# leaf_xcvr_rs485_bro.net
KiCad netlist of a schematic drawn in EAGLE
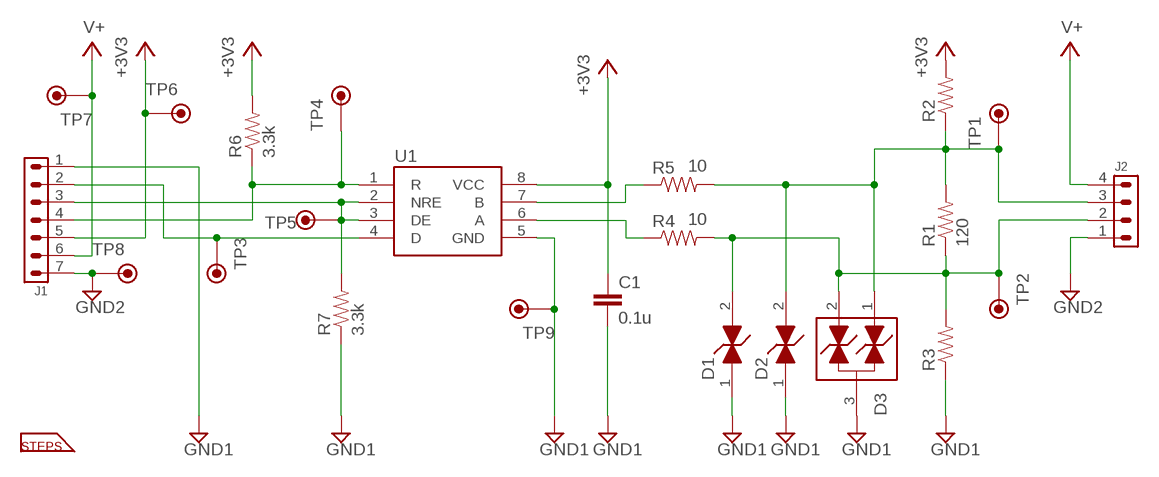
[diagram p0: schematic, sheet 1]

(export (version "E")
  (design (tool "Eeschema 10.0.6"))
  (components
    (comp (ref "C1")
      (value "0.1u")
      (footprint "eagle-import:0603")
      (libsource (lib "eagle-import") (part "0603_CAP"))
    )
    (comp (ref "D1")
      (value "TVS_DO-214AA")
      (footprint "eagle-import:DO-214AA_LITTELFUSE")
      (libsource (lib "eagle-import") (part "TVS_DO-214AA"))
    )
    (comp (ref "D2")
      (value "TVS_DO-214AA")
      (footprint "eagle-import:DO-214AA_LITTELFUSE")
      (libsource (lib "eagle-import") (part "TVS_DO-214AA"))
    )
    (comp (ref "D3")
      (value "TVS_SOT-23")
      (footprint "eagle-import:SOT-23_ONSEMI")
      (libsource (lib "eagle-import") (part "TVS_SOT-23"))
    )
    (comp (ref "J1")
      (value "CONN_7X1_JST_PA")
      (footprint "eagle-import:CONN_7X1_JST_PA")
      (libsource (lib "eagle-import") (part "CONN_7X1_JST_PA"))
    )
    (comp (ref "J2")
      (value "CONN_4X1_JST_PA")
      (footprint "eagle-import:CONN_4X1_JST_PA")
      (libsource (lib "eagle-import") (part "CONN_4X1_JST_PA"))
    )
    (comp (ref "R1")
      (value "120")
      (footprint "eagle-import:0603")
      (libsource (lib "eagle-import") (part "0603_RES"))
    )
    (comp (ref "R2")
      (value "0603_RES")
      (footprint "eagle-import:0603")
      (libsource (lib "eagle-import") (part "0603_RES"))
    )
    (comp (ref "R3")
      (value "0603_RES")
      (footprint "eagle-import:0603")
      (libsource (lib "eagle-import") (part "0603_RES"))
    )
    (comp (ref "R4")
      (value "10")
      (footprint "eagle-import:0603")
      (libsource (lib "eagle-import") (part "0603_RES"))
    )
    (comp (ref "R5")
      (value "10")
      (footprint "eagle-import:0603")
      (libsource (lib "eagle-import") (part "0603_RES"))
    )
    (comp (ref "R6")
      (value "3.3k")
      (footprint "eagle-import:0603")
      (libsource (lib "eagle-import") (part "0603_RES"))
    )
    (comp (ref "R7")
      (value "3.3k")
      (footprint "eagle-import:0603")
      (libsource (lib "eagle-import") (part "0603_RES"))
    )
    (comp (ref "TP1")
      (value "TP1")
      (footprint "eagle-import:TP1")
      (libsource (lib "eagle-import") (part "TP1"))
    )
    (comp (ref "TP2")
      (value "TP1")
      (footprint "eagle-import:TP1")
      (libsource (lib "eagle-import") (part "TP1"))
    )
    (comp (ref "TP3")
      (value "TP1")
      (footprint "eagle-import:TP1")
      (libsource (lib "eagle-import") (part "TP1"))
    )
    (comp (ref "TP4")
      (value "TP1")
      (footprint "eagle-import:TP1")
      (libsource (lib "eagle-import") (part "TP1"))
    )
    (comp (ref "TP5")
      (value "TP1")
      (footprint "eagle-import:TP1")
      (libsource (lib "eagle-import") (part "TP1"))
    )
    (comp (ref "TP6")
      (value "TP1")
      (footprint "eagle-import:TP1")
      (libsource (lib "eagle-import") (part "TP1"))
    )
    (comp (ref "TP7")
      (value "TP1")
      (footprint "eagle-import:TP1")
      (libsource (lib "eagle-import") (part "TP1"))
    )
    (comp (ref "TP8")
      (value "TP1")
      (footprint "eagle-import:TP1")
      (libsource (lib "eagle-import") (part "TP1"))
    )
    (comp (ref "TP9")
      (value "TP1")
      (footprint "eagle-import:TP1")
      (libsource (lib "eagle-import") (part "TP1"))
    )
    (comp (ref "U$1")
      (value "STEPS_LOGO")
      (footprint "eagle-import:STEPS_LOGO")
      (libsource (lib "eagle-import") (part "STEPS_LOGO"))
    )
    (comp (ref "U1")
      (value "RS485_XCVR_SN65HVD178X")
      (footprint "eagle-import:SOIC_08_TI")
      (libsource (lib "eagle-import") (part "RS485_XCVR_SN65HVD178X"))
    )
  )
  (nets
    (net (code "1") (name "+3V3") (class "Default")
      (node (ref "C1") (pin "P$1") (pinfunction "1_P$1") (pintype "passive"))
      (node (ref "J1") (pin "5") (pinfunction "5_5") (pintype "bidirectional"))
      (node (ref "R2") (pin "P$2") (pinfunction "2_P$2") (pintype "passive"))
      (node (ref "R6") (pin "P$2") (pinfunction "2_P$2") (pintype "passive"))
      (node (ref "TP6") (pin "P$1") (pinfunction "P$1_P$1") (pintype "bidirectional"))
      (node (ref "U1") (pin "8") (pinfunction "VCC_8") (pintype "bidirectional"))
    )
    (net (code "2") (name "GND1") (class "Default")
      (node (ref "C1") (pin "P$2") (pinfunction "2_P$2") (pintype "passive"))
      (node (ref "D1") (pin "1") (pinfunction "1_1") (pintype "bidirectional"))
      (node (ref "D2") (pin "1") (pinfunction "1_1") (pintype "bidirectional"))
      (node (ref "D3") (pin "3") (pinfunction "3_3") (pintype "bidirectional"))
      (node (ref "J1") (pin "1") (pinfunction "1_1") (pintype "bidirectional"))
      (node (ref "R3") (pin "P$1") (pinfunction "1_P$1") (pintype "passive"))
      (node (ref "R7") (pin "P$1") (pinfunction "1_P$1") (pintype "passive"))
      (node (ref "TP9") (pin "P$1") (pinfunction "P$1_P$1") (pintype "bidirectional"))
      (node (ref "U1") (pin "5") (pinfunction "GND_5") (pintype "bidirectional"))
    )
    (net (code "3") (name "GND2") (class "Default")
      (node (ref "J1") (pin "7") (pinfunction "7_7") (pintype "bidirectional"))
      (node (ref "J2") (pin "1") (pinfunction "1_1") (pintype "bidirectional"))
      (node (ref "TP8") (pin "P$1") (pinfunction "P$1_P$1") (pintype "bidirectional"))
    )
    (net (code "4") (name "Net-(R1-1)") (class "Default")
      (node (ref "D1") (pin "2") (pinfunction "2_2") (pintype "bidirectional"))
      (node (ref "D3") (pin "2") (pinfunction "2_2") (pintype "bidirectional"))
      (node (ref "J2") (pin "2") (pinfunction "2_2") (pintype "bidirectional"))
      (node (ref "R1") (pin "P$1") (pinfunction "1_P$1") (pintype "passive"))
      (node (ref "R3") (pin "P$2") (pinfunction "2_P$2") (pintype "passive"))
      (node (ref "R4") (pin "P$2") (pinfunction "2_P$2") (pintype "passive"))
      (node (ref "TP2") (pin "P$1") (pinfunction "P$1_P$1") (pintype "bidirectional"))
    )
    (net (code "5") (name "Net-(R1-2)") (class "Default")
      (node (ref "D2") (pin "2") (pinfunction "2_2") (pintype "bidirectional"))
      (node (ref "D3") (pin "1") (pinfunction "1_1") (pintype "bidirectional"))
      (node (ref "J2") (pin "3") (pinfunction "3_3") (pintype "bidirectional"))
      (node (ref "R1") (pin "P$2") (pinfunction "2_P$2") (pintype "passive"))
      (node (ref "R2") (pin "P$1") (pinfunction "1_P$1") (pintype "passive"))
      (node (ref "R5") (pin "P$2") (pinfunction "2_P$2") (pintype "passive"))
      (node (ref "TP1") (pin "P$1") (pinfunction "P$1_P$1") (pintype "bidirectional"))
    )
    (net (code "6") (name "Net-(R4-1)") (class "Default")
      (node (ref "R4") (pin "P$1") (pinfunction "1_P$1") (pintype "passive"))
      (node (ref "U1") (pin "6") (pinfunction "A_6") (pintype "bidirectional"))
    )
    (net (code "7") (name "Net-(R5-1)") (class "Default")
      (node (ref "R5") (pin "P$1") (pinfunction "1_P$1") (pintype "passive"))
      (node (ref "U1") (pin "7") (pinfunction "B_7") (pintype "bidirectional"))
    )
    (net (code "8") (name "Net-(R6-1)") (class "Default")
      (node (ref "J1") (pin "4") (pinfunction "4_4") (pintype "bidirectional"))
      (node (ref "R6") (pin "P$1") (pinfunction "1_P$1") (pintype "passive"))
      (node (ref "TP4") (pin "P$1") (pinfunction "P$1_P$1") (pintype "bidirectional"))
      (node (ref "U1") (pin "1") (pinfunction "R_1") (pintype "bidirectional"))
    )
    (net (code "9") (name "Net-(R7-2)") (class "Default")
      (node (ref "J1") (pin "3") (pinfunction "3_3") (pintype "bidirectional"))
      (node (ref "R7") (pin "P$2") (pinfunction "2_P$2") (pintype "passive"))
      (node (ref "TP5") (pin "P$1") (pinfunction "P$1_P$1") (pintype "bidirectional"))
      (node (ref "U1") (pin "2") (pinfunction "NRE_2") (pintype "bidirectional"))
      (node (ref "U1") (pin "3") (pinfunction "DE_3") (pintype "bidirectional"))
    )
    (net (code "10") (name "Net-(U1-D)") (class "Default")
      (node (ref "J1") (pin "2") (pinfunction "2_2") (pintype "bidirectional"))
      (node (ref "TP3") (pin "P$1") (pinfunction "P$1_P$1") (pintype "bidirectional"))
      (node (ref "U1") (pin "4") (pinfunction "D_4") (pintype "bidirectional"))
    )
    (net (code "11") (name "V+") (class "Default")
      (node (ref "J1") (pin "6") (pinfunction "6_6") (pintype "bidirectional"))
      (node (ref "J2") (pin "4") (pinfunction "4_4") (pintype "bidirectional"))
      (node (ref "TP7") (pin "P$1") (pinfunction "P$1_P$1") (pintype "bidirectional"))
    )
  )
)
